# mx25l25645gz2i-08g.net
KiCad netlist of a schematic drawn in Altium Designer
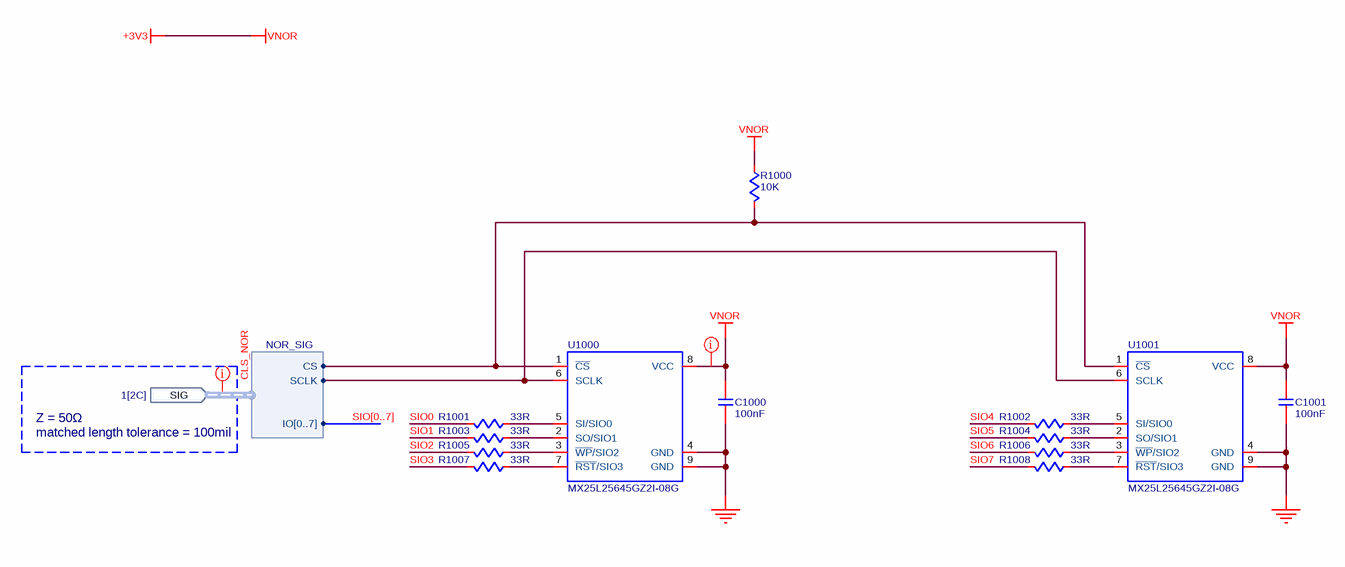
[diagram p0: mx25l25645gz2i-08g.SchDoc]

(export (version "E")
  (design (tool "Eeschema 10.0.6"))
  (components
    (comp (ref "C1000")
      (value "100nF")
      (footprint "mw:C0402")
      (fields (field (name "VOLTAGE") "25V") (field (name "Comment") "C-NOMO"))
      (libsource (lib "mw") (part "C-NOMO"))
    )
    (comp (ref "C1001")
      (value "100nF")
      (footprint "mw:C0402")
      (fields (field (name "VOLTAGE") "25V") (field (name "Comment") "C-NOMO"))
      (libsource (lib "mw") (part "C-NOMO"))
    )
    (comp (ref "R1000")
      (value "10K")
      (footprint "mw:R0402")
      (fields (field (name "Comment") "R"))
      (libsource (lib "mw") (part "R"))
    )
    (comp (ref "R1001")
      (value "33R")
      (footprint "mw:R0402")
      (fields (field (name "Comment") "R"))
      (libsource (lib "mw") (part "R"))
    )
    (comp (ref "R1002")
      (value "33R")
      (footprint "mw:R0402")
      (fields (field (name "Comment") "R"))
      (libsource (lib "mw") (part "R"))
    )
    (comp (ref "R1003")
      (value "33R")
      (footprint "mw:R0402")
      (fields (field (name "Comment") "R"))
      (libsource (lib "mw") (part "R"))
    )
    (comp (ref "R1004")
      (value "33R")
      (footprint "mw:R0402")
      (fields (field (name "Comment") "R"))
      (libsource (lib "mw") (part "R"))
    )
    (comp (ref "R1005")
      (value "33R")
      (footprint "mw:R0402")
      (fields (field (name "Comment") "R"))
      (libsource (lib "mw") (part "R"))
    )
    (comp (ref "R1006")
      (value "33R")
      (footprint "mw:R0402")
      (fields (field (name "Comment") "R"))
      (libsource (lib "mw") (part "R"))
    )
    (comp (ref "R1007")
      (value "33R")
      (footprint "mw:R0402")
      (fields (field (name "Comment") "R"))
      (libsource (lib "mw") (part "R"))
    )
    (comp (ref "R1008")
      (value "33R")
      (footprint "mw:R0402")
      (fields (field (name "Comment") "R"))
      (libsource (lib "mw") (part "R"))
    )
    (comp (ref "U1000")
      (value "MX25L25645GZ2I-08G")
      (footprint "MX25L25645GZ2I-08G")
      (libsource (lib "mw") (part "MX25L25645GZ2I-08G"))
    )
    (comp (ref "U1001")
      (value "MX25L25645GZ2I-08G")
      (footprint "MX25L25645GZ2I-08G")
      (libsource (lib "mw") (part "MX25L25645GZ2I-08G"))
    )
  )
  (nets
    (net (code "2") (name "+3V3") (class "Default")
      (node (ref "C1000") (pin "2") (pinfunction "2_2") (pintype "passive"))
      (node (ref "C1001") (pin "2") (pinfunction "2_2") (pintype "passive"))
      (node (ref "R1000") (pin "2") (pinfunction "2_2") (pintype "passive"))
      (node (ref "U1000") (pin "8") (pinfunction "VCC_8") (pintype "passive"))
      (node (ref "U1001") (pin "8") (pinfunction "VCC_8") (pintype "passive"))
    )
    (net (code "3") (name "/SIO0") (class "Default")
      (node (ref "R1001") (pin "1") (pinfunction "1_1") (pintype "passive"))
    )
    (net (code "4") (name "/SIO1") (class "Default")
      (node (ref "R1003") (pin "1") (pinfunction "1_1") (pintype "passive"))
    )
    (net (code "5") (name "/SIO2") (class "Default")
      (node (ref "R1005") (pin "1") (pinfunction "1_1") (pintype "passive"))
    )
    (net (code "6") (name "/SIO3") (class "Default")
      (node (ref "R1007") (pin "1") (pinfunction "1_1") (pintype "passive"))
    )
    (net (code "7") (name "/SIO4") (class "Default")
      (node (ref "R1002") (pin "1") (pinfunction "1_1") (pintype "passive"))
    )
    (net (code "8") (name "/SIO5") (class "Default")
      (node (ref "R1004") (pin "1") (pinfunction "1_1") (pintype "passive"))
    )
    (net (code "9") (name "/SIO6") (class "Default")
      (node (ref "R1006") (pin "1") (pinfunction "1_1") (pintype "passive"))
    )
    (net (code "10") (name "/SIO7") (class "Default")
      (node (ref "R1008") (pin "1") (pinfunction "1_1") (pintype "passive"))
    )
    (net (code "13") (name "GND") (class "Default")
      (node (ref "C1000") (pin "1") (pinfunction "1_1") (pintype "passive"))
      (node (ref "C1001") (pin "1") (pinfunction "1_1") (pintype "passive"))
      (node (ref "U1000") (pin "4") (pinfunction "GND_4") (pintype "passive"))
      (node (ref "U1000") (pin "9") (pinfunction "GND_9") (pintype "passive"))
      (node (ref "U1001") (pin "4") (pinfunction "GND_4") (pintype "passive"))
      (node (ref "U1001") (pin "9") (pinfunction "GND_9") (pintype "passive"))
    )
    (net (code "14") (name "Net-(U1000-SCLK)") (class "Default")
      (node (ref "U1000") (pin "6") (pinfunction "SCLK_6") (pintype "passive"))
      (node (ref "U1001") (pin "6") (pinfunction "SCLK_6") (pintype "passive"))
    )
    (net (code "15") (name "Net-(U1000-SI{slash}SIO0)") (class "Default")
      (node (ref "R1001") (pin "2") (pinfunction "2_2") (pintype "passive"))
      (node (ref "U1000") (pin "5") (pinfunction "SI/SIO0_5") (pintype "passive"))
    )
    (net (code "16") (name "Net-(U1000-SO{slash}SIO1)") (class "Default")
      (node (ref "R1003") (pin "2") (pinfunction "2_2") (pintype "passive"))
      (node (ref "U1000") (pin "2") (pinfunction "SO/SIO1_2") (pintype "passive"))
    )
    (net (code "17") (name "Net-(U1000-~{CS})") (class "Default")
      (node (ref "R1000") (pin "1") (pinfunction "1_1") (pintype "passive"))
      (node (ref "U1000") (pin "1") (pinfunction "~{CS}_1") (pintype "passive"))
      (node (ref "U1001") (pin "1") (pinfunction "~{CS}_1") (pintype "passive"))
    )
    (net (code "18") (name "Net-(U1000-~{RST}{slash}SIO3)") (class "Default")
      (node (ref "R1007") (pin "2") (pinfunction "2_2") (pintype "passive"))
      (node (ref "U1000") (pin "7") (pinfunction "~{RST}/SIO3_7") (pintype "passive"))
    )
    (net (code "19") (name "Net-(U1000-~{WP}{slash}SIO2)") (class "Default")
      (node (ref "R1005") (pin "2") (pinfunction "2_2") (pintype "passive"))
      (node (ref "U1000") (pin "3") (pinfunction "~{WP}/SIO2_3") (pintype "passive"))
    )
    (net (code "20") (name "Net-(U1001-SI{slash}SIO0)") (class "Default")
      (node (ref "R1002") (pin "2") (pinfunction "2_2") (pintype "passive"))
      (node (ref "U1001") (pin "5") (pinfunction "SI/SIO0_5") (pintype "passive"))
    )
    (net (code "21") (name "Net-(U1001-SO{slash}SIO1)") (class "Default")
      (node (ref "R1004") (pin "2") (pinfunction "2_2") (pintype "passive"))
      (node (ref "U1001") (pin "2") (pinfunction "SO/SIO1_2") (pintype "passive"))
    )
    (net (code "22") (name "Net-(U1001-~{RST}{slash}SIO3)") (class "Default")
      (node (ref "R1008") (pin "2") (pinfunction "2_2") (pintype "passive"))
      (node (ref "U1001") (pin "7") (pinfunction "~{RST}/SIO3_7") (pintype "passive"))
    )
    (net (code "23") (name "Net-(U1001-~{WP}{slash}SIO2)") (class "Default")
      (node (ref "R1006") (pin "2") (pinfunction "2_2") (pintype "passive"))
      (node (ref "U1001") (pin "3") (pinfunction "~{WP}/SIO2_3") (pintype "passive"))
    )
  )
)
